# e1_tap.net
KiCad netlist of a schematic drawn in EAGLE
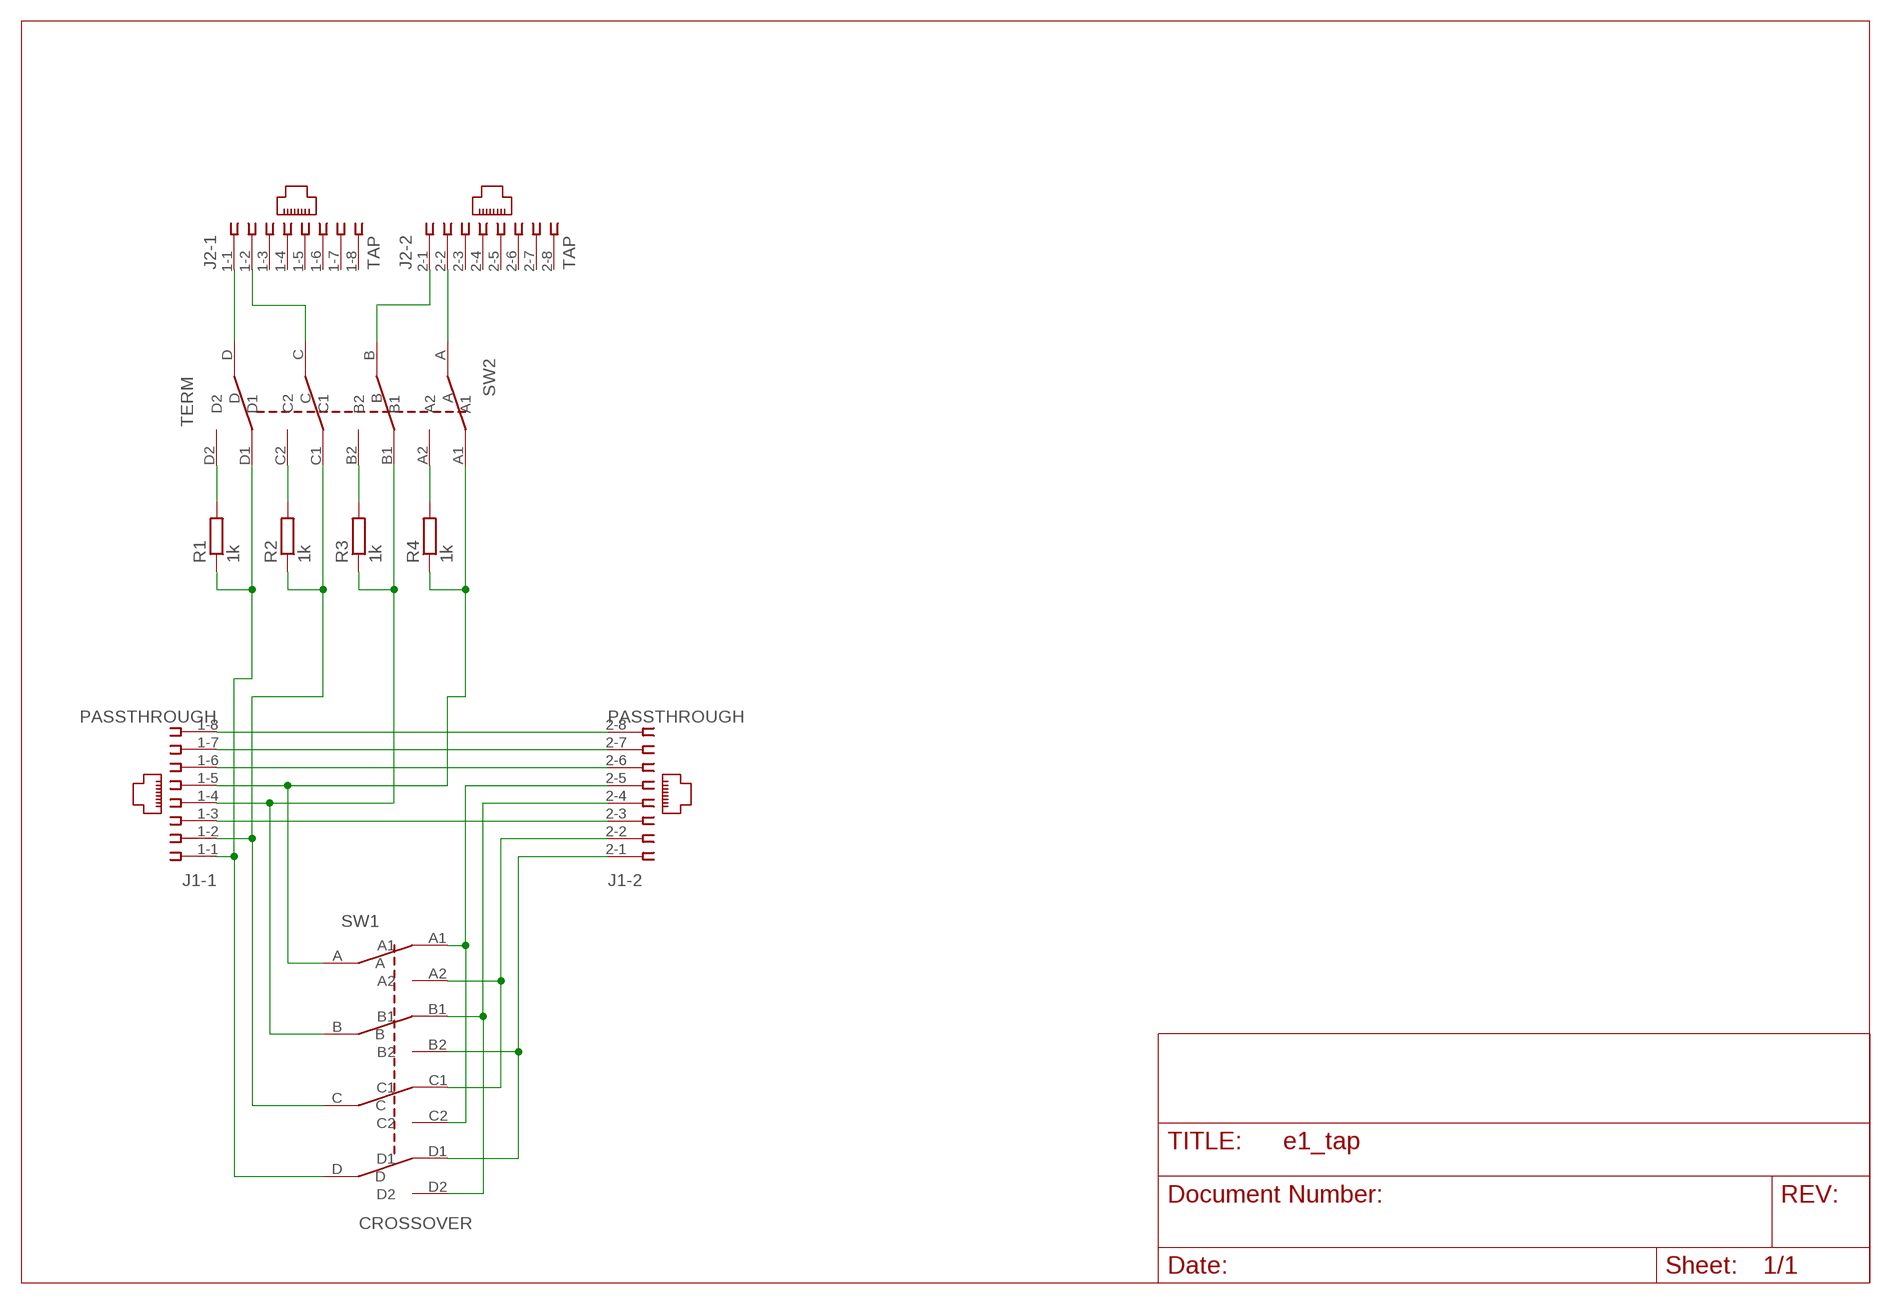
[diagram p0: schematic, sheet 1]

(export (version "E")
  (design (tool "Eeschema 10.0.6"))
  (components
    (comp (ref "J1")
      (value "PASSTHROUGH")
      (footprint "eagle-import:557560-1")
      (description "CONN MOD JACK 8P8C R/A UNSHLD")
      (fields
        (field (name "MANUFACTURER") "TE Connectivity AMP Connectors")
        (field (name "MANUFACTURERPARTNUMBER") "5557560-1")
        (field (name "CLASS") "CONNECTOR\\JUMPER")
        (field (name "LINK") "https://www.digikey.de/product-detail/en/te-connectivity-amp-connectors/5557560-1/A31449-ND/769593")
        (field (name "POPULATED") "TRUE")
        (field (name "ROHSCERTIFICATE") "UNKNOWN ROHS CERTIFICATE")
        (field (name "SOURCE") "DIGIKEY")
        (field (name "SOURCEPARTNUMBER") "A31449-ND")
      )
      (libsource (lib "eagle-import") (part "557560-1"))
    )
    (comp (ref "J2")
      (value "TAP")
      (footprint "eagle-import:557560-1")
      (description "CONN MOD JACK 8P8C R/A UNSHLD")
      (fields
        (field (name "CLASS") "CONNECTOR\\JUMPER")
        (field (name "LINK") "https://www.digikey.de/product-detail/en/te-connectivity-amp-connectors/5557560-1/A31449-ND/769593")
        (field (name "MANUFACTURER") "TE Connectivity AMP Connectors")
        (field (name "MANUFACTURERPARTNUMBER") "5557560-1")
        (field (name "POPULATED") "TRUE")
        (field (name "ROHSCERTIFICATE") "UNKNOWN ROHS CERTIFICATE")
        (field (name "SOURCE") "DIGIKEY")
        (field (name "SOURCEPARTNUMBER") "A31449-ND")
      )
      (libsource (lib "eagle-import") (part "557560-1"))
    )
    (comp (ref "R1")
      (value "1k")
      (footprint "eagle-import:R0603")
      (description "RES SMD 1K OHM 1% 1/10W 0603")
      (fields (field (name "MANUFACTURER") "Yageo") (field (name "MANUFACTURERPARTNUMBER") "RC0603FR-071KL"))
      (libsource (lib "eagle-import") (part "R-EU_R0603"))
    )
    (comp (ref "R2")
      (value "1k")
      (footprint "eagle-import:R0603")
      (description "RES SMD 1K OHM 1% 1/10W 0603")
      (fields (field (name "MANUFACTURER") "Yageo") (field (name "MANUFACTURERPARTNUMBER") "RC0603FR-071KL"))
      (libsource (lib "eagle-import") (part "R-EU_R0603"))
    )
    (comp (ref "R3")
      (value "1k")
      (footprint "eagle-import:R0603")
      (description "RES SMD 1K OHM 1% 1/10W 0603")
      (fields (field (name "MANUFACTURER") "Yageo") (field (name "MANUFACTURERPARTNUMBER") "RC0603FR-071KL"))
      (libsource (lib "eagle-import") (part "R-EU_R0603"))
    )
    (comp (ref "R4")
      (value "1k")
      (footprint "eagle-import:R0603")
      (description "RES SMD 1K OHM 1% 1/10W 0603")
      (fields (field (name "MANUFACTURER") "Yageo") (field (name "MANUFACTURERPARTNUMBER") "RC0603FR-071KL"))
      (libsource (lib "eagle-import") (part "R-EU_R0603"))
    )
    (comp (ref "SW1")
      (value "CROSSOVER")
      (footprint "eagle-import:4PDT_DIL12")
      (description "SWITCH SLIDE 4PDT 300MA 115V")
      (fields
        (field (name "MANUFACTURER") "TE Connectivity ALCOSWITCH Switches")
        (field (name "MANUFACTURERPARTNUMBER") "1-1825010-3")
      )
      (libsource (lib "eagle-import") (part "SWITCH_4PDT"))
    )
    (comp (ref "SW2")
      (value "TERM")
      (footprint "eagle-import:4PDT_DIL12")
      (description "SWITCH SLIDE 4PDT 300MA 115V")
      (fields
        (field (name "MANUFACTURER") "TE Connectivity ALCOSWITCH Switches")
        (field (name "MANUFACTURERPARTNUMBER") "1-1825010-3")
      )
      (libsource (lib "eagle-import") (part "SWITCH_4PDT"))
    )
  )
  (nets
    (net (code "1") (name "Net-(J1A-1)") (class "Default")
      (node (ref "J1") (pin "1-1") (pinfunction "1_1-1") (pintype "passive"))
      (node (ref "R1") (pin "1") (pinfunction "1_1") (pintype "passive"))
      (node (ref "SW1") (pin "D") (pinfunction "D_D") (pintype "bidirectional"))
      (node (ref "SW2") (pin "D1") (pinfunction "D1_D1") (pintype "bidirectional"))
    )
    (net (code "2") (name "Net-(J1A-2)") (class "Default")
      (node (ref "J1") (pin "1-2") (pinfunction "2_1-2") (pintype "passive"))
      (node (ref "R2") (pin "1") (pinfunction "1_1") (pintype "passive"))
      (node (ref "SW1") (pin "C") (pinfunction "C_C") (pintype "bidirectional"))
      (node (ref "SW2") (pin "C1") (pinfunction "C1_C1") (pintype "bidirectional"))
    )
    (net (code "3") (name "Net-(J1A-3)") (class "Default")
      (node (ref "J1") (pin "1-3") (pinfunction "3_1-3") (pintype "passive"))
      (node (ref "J1") (pin "2-3") (pinfunction "3_2-3") (pintype "passive"))
    )
    (net (code "4") (name "Net-(J1A-4)") (class "Default")
      (node (ref "J1") (pin "1-4") (pinfunction "4_1-4") (pintype "passive"))
      (node (ref "R3") (pin "1") (pinfunction "1_1") (pintype "passive"))
      (node (ref "SW1") (pin "B") (pinfunction "B_B") (pintype "bidirectional"))
      (node (ref "SW2") (pin "B1") (pinfunction "B1_B1") (pintype "bidirectional"))
    )
    (net (code "5") (name "Net-(J1A-5)") (class "Default")
      (node (ref "J1") (pin "1-5") (pinfunction "5_1-5") (pintype "passive"))
      (node (ref "R4") (pin "1") (pinfunction "1_1") (pintype "passive"))
      (node (ref "SW1") (pin "A") (pinfunction "A_A") (pintype "bidirectional"))
      (node (ref "SW2") (pin "A1") (pinfunction "A1_A1") (pintype "bidirectional"))
    )
    (net (code "6") (name "Net-(J1A-6)") (class "Default")
      (node (ref "J1") (pin "1-6") (pinfunction "6_1-6") (pintype "passive"))
      (node (ref "J1") (pin "2-6") (pinfunction "6_2-6") (pintype "passive"))
    )
    (net (code "7") (name "Net-(J1A-7)") (class "Default")
      (node (ref "J1") (pin "1-7") (pinfunction "7_1-7") (pintype "passive"))
      (node (ref "J1") (pin "2-7") (pinfunction "7_2-7") (pintype "passive"))
    )
    (net (code "8") (name "Net-(J1A-8)") (class "Default")
      (node (ref "J1") (pin "1-8") (pinfunction "8_1-8") (pintype "passive"))
      (node (ref "J1") (pin "2-8") (pinfunction "8_2-8") (pintype "passive"))
    )
    (net (code "9") (name "Net-(J1B-1)") (class "Default")
      (node (ref "J1") (pin "2-1") (pinfunction "1_2-1") (pintype "passive"))
      (node (ref "SW1") (pin "B2") (pinfunction "B2_B2") (pintype "bidirectional"))
      (node (ref "SW1") (pin "D1") (pinfunction "D1_D1") (pintype "bidirectional"))
    )
    (net (code "10") (name "Net-(J1B-2)") (class "Default")
      (node (ref "J1") (pin "2-2") (pinfunction "2_2-2") (pintype "passive"))
      (node (ref "SW1") (pin "A2") (pinfunction "A2_A2") (pintype "bidirectional"))
      (node (ref "SW1") (pin "C1") (pinfunction "C1_C1") (pintype "bidirectional"))
    )
    (net (code "11") (name "Net-(J1B-4)") (class "Default")
      (node (ref "J1") (pin "2-4") (pinfunction "4_2-4") (pintype "passive"))
      (node (ref "SW1") (pin "B1") (pinfunction "B1_B1") (pintype "bidirectional"))
      (node (ref "SW1") (pin "D2") (pinfunction "D2_D2") (pintype "bidirectional"))
    )
    (net (code "12") (name "Net-(J1B-5)") (class "Default")
      (node (ref "J1") (pin "2-5") (pinfunction "5_2-5") (pintype "passive"))
      (node (ref "SW1") (pin "A1") (pinfunction "A1_A1") (pintype "bidirectional"))
      (node (ref "SW1") (pin "C2") (pinfunction "C2_C2") (pintype "bidirectional"))
    )
    (net (code "13") (name "Net-(J2A-1)") (class "Default")
      (node (ref "J2") (pin "1-1") (pinfunction "1_1-1") (pintype "passive"))
      (node (ref "SW2") (pin "D") (pinfunction "D_D") (pintype "bidirectional"))
    )
    (net (code "14") (name "Net-(J2A-2)") (class "Default")
      (node (ref "J2") (pin "1-2") (pinfunction "2_1-2") (pintype "passive"))
      (node (ref "SW2") (pin "C") (pinfunction "C_C") (pintype "bidirectional"))
    )
    (net (code "15") (name "Net-(J2B-1)") (class "Default")
      (node (ref "J2") (pin "2-1") (pinfunction "1_2-1") (pintype "passive"))
      (node (ref "SW2") (pin "B") (pinfunction "B_B") (pintype "bidirectional"))
    )
    (net (code "16") (name "Net-(J2B-2)") (class "Default")
      (node (ref "J2") (pin "2-2") (pinfunction "2_2-2") (pintype "passive"))
      (node (ref "SW2") (pin "A") (pinfunction "A_A") (pintype "bidirectional"))
    )
    (net (code "17") (name "Net-(R1-Pad2)") (class "Default")
      (node (ref "R1") (pin "2") (pinfunction "2_2") (pintype "passive"))
      (node (ref "SW2") (pin "D2") (pinfunction "D2_D2") (pintype "bidirectional"))
    )
    (net (code "18") (name "Net-(R2-Pad2)") (class "Default")
      (node (ref "R2") (pin "2") (pinfunction "2_2") (pintype "passive"))
      (node (ref "SW2") (pin "C2") (pinfunction "C2_C2") (pintype "bidirectional"))
    )
    (net (code "19") (name "Net-(R3-Pad2)") (class "Default")
      (node (ref "R3") (pin "2") (pinfunction "2_2") (pintype "passive"))
      (node (ref "SW2") (pin "B2") (pinfunction "B2_B2") (pintype "bidirectional"))
    )
    (net (code "20") (name "Net-(R4-Pad2)") (class "Default")
      (node (ref "R4") (pin "2") (pinfunction "2_2") (pintype "passive"))
      (node (ref "SW2") (pin "A2") (pinfunction "A2_A2") (pintype "bidirectional"))
    )
    (net (code "21") (name "unconnected-(J2A-3-Pad1-3)") (class "Default")
      (node (ref "J2") (pin "1-3") (pinfunction "3_1-3") (pintype "passive"))
    )
    (net (code "22") (name "unconnected-(J2A-4-Pad1-4)") (class "Default")
      (node (ref "J2") (pin "1-4") (pinfunction "4_1-4") (pintype "passive"))
    )
    (net (code "23") (name "unconnected-(J2A-5-Pad1-5)") (class "Default")
      (node (ref "J2") (pin "1-5") (pinfunction "5_1-5") (pintype "passive"))
    )
    (net (code "24") (name "unconnected-(J2A-6-Pad1-6)") (class "Default")
      (node (ref "J2") (pin "1-6") (pinfunction "6_1-6") (pintype "passive"))
    )
    (net (code "25") (name "unconnected-(J2A-7-Pad1-7)") (class "Default")
      (node (ref "J2") (pin "1-7") (pinfunction "7_1-7") (pintype "passive"))
    )
    (net (code "26") (name "unconnected-(J2A-8-Pad1-8)") (class "Default")
      (node (ref "J2") (pin "1-8") (pinfunction "8_1-8") (pintype "passive"))
    )
    (net (code "27") (name "unconnected-(J2B-3-Pad2-3)") (class "Default")
      (node (ref "J2") (pin "2-3") (pinfunction "3_2-3") (pintype "passive"))
    )
    (net (code "28") (name "unconnected-(J2B-4-Pad2-4)") (class "Default")
      (node (ref "J2") (pin "2-4") (pinfunction "4_2-4") (pintype "passive"))
    )
    (net (code "29") (name "unconnected-(J2B-5-Pad2-5)") (class "Default")
      (node (ref "J2") (pin "2-5") (pinfunction "5_2-5") (pintype "passive"))
    )
    (net (code "30") (name "unconnected-(J2B-6-Pad2-6)") (class "Default")
      (node (ref "J2") (pin "2-6") (pinfunction "6_2-6") (pintype "passive"))
    )
    (net (code "31") (name "unconnected-(J2B-7-Pad2-7)") (class "Default")
      (node (ref "J2") (pin "2-7") (pinfunction "7_2-7") (pintype "passive"))
    )
    (net (code "32") (name "unconnected-(J2B-8-Pad2-8)") (class "Default")
      (node (ref "J2") (pin "2-8") (pinfunction "8_2-8") (pintype "passive"))
    )
  )
)
